# Fuel-Gauge.net
KiCad netlist of a schematic drawn in Altium Designer
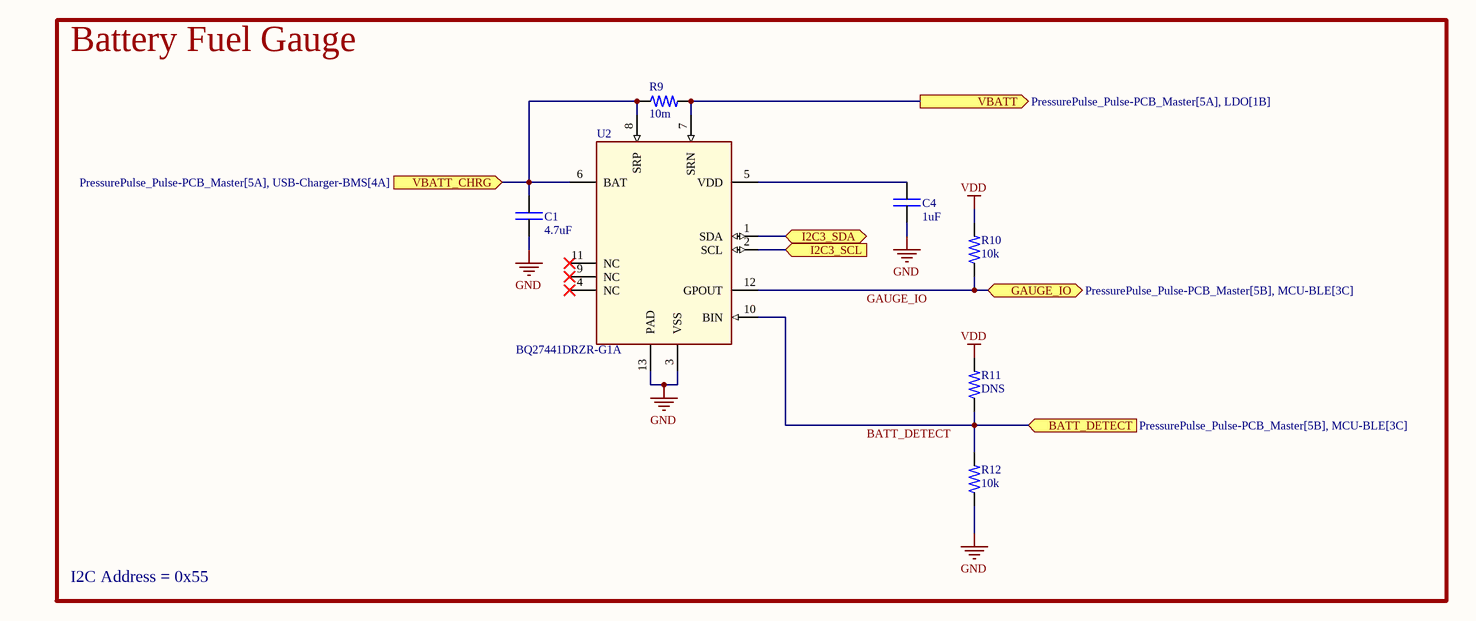
[diagram p0: Fuel-Gauge.SchDoc]

(export (version "E")
  (design (tool "Eeschema 10.0.6"))
  (components
    (comp (ref "C1")
      (value "4.7uF")
      (footprint "PressurePulse:0402C")
      (description "Capacitor")
      (fields (field (name "Comment") "CAP"))
      (libsource (lib "PressurePulse") (part "CAP"))
    )
    (comp (ref "C4")
      (value "1uF")
      (footprint "PressurePulse:0402C")
      (description "Capacitor")
      (fields (field (name "Comment") "CAP"))
      (libsource (lib "PressurePulse") (part "CAP"))
    )
    (comp (ref "R9")
      (value "10m")
      (footprint "PressurePulse:0805R")
      (description "Resistor")
      (fields (field (name "MFR") "YAGEO") (field (name "TOLERANCE") "1%"))
      (libsource (lib "PressurePulse") (part "RES"))
    )
    (comp (ref "R10")
      (value "10k")
      (footprint "PressurePulse:0402R")
      (description "Resistor")
      (fields (field (name "Comment") "RES"))
      (libsource (lib "PressurePulse") (part "RES"))
    )
    (comp (ref "R11")
      (value "DNS")
      (footprint "PressurePulse:0402R")
      (description "Resistor")
      (fields (field (name "Comment") "RES"))
      (libsource (lib "PressurePulse") (part "RES"))
    )
    (comp (ref "R12")
      (value "10k")
      (footprint "PressurePulse:0402R")
      (description "Resistor")
      (fields (field (name "Comment") "RES"))
      (libsource (lib "PressurePulse") (part "RES"))
    )
    (comp (ref "U2")
      (value "BQ27441DRZR-G1A")
      (footprint "PressurePulse:bq27441-G1")
      (description "No Description Available")
      (fields (field (name "MFR") "Texas Instruments"))
      (libsource (lib "PressurePulse") (part "BATT FUEL GAUGE"))
    )
  )
  (nets
    (net (code "1") (name "/BATT_DETECT") (class "Default")
      (node (ref "R11") (pin "1") (pinfunction "1_1") (pintype "passive"))
      (node (ref "R12") (pin "2") (pinfunction "2_2") (pintype "passive"))
      (node (ref "U2") (pin "10") (pinfunction "BIN_10") (pintype "input"))
    )
    (net (code "2") (name "/GAUGE_IO") (class "Default")
      (node (ref "R10") (pin "1") (pinfunction "1_1") (pintype "passive"))
      (node (ref "U2") (pin "12") (pinfunction "GPOUT_12") (pintype "open_collector"))
    )
    (net (code "3") (name "/I2C3_SCL") (class "Default")
      (node (ref "U2") (pin "2") (pinfunction "SCL_2") (pintype "bidirectional"))
    )
    (net (code "4") (name "/I2C3_SDA") (class "Default")
      (node (ref "U2") (pin "1") (pinfunction "SDA_1") (pintype "bidirectional"))
    )
    (net (code "5") (name "/VBATT") (class "Default")
      (node (ref "R9") (pin "2") (pinfunction "2_2") (pintype "passive"))
      (node (ref "U2") (pin "7") (pinfunction "SRN_7") (pintype "input"))
    )
    (net (code "6") (name "/VBATT_CHRG") (class "Default")
      (node (ref "C1") (pin "2") (pinfunction "2_2") (pintype "passive"))
      (node (ref "R9") (pin "1") (pinfunction "1_1") (pintype "passive"))
      (node (ref "U2") (pin "6") (pinfunction "BAT_6") (pintype "power_in"))
      (node (ref "U2") (pin "8") (pinfunction "SRP_8") (pintype "input"))
    )
    (net (code "7") (name "GND") (class "Default")
      (node (ref "C1") (pin "1") (pinfunction "1_1") (pintype "passive"))
      (node (ref "C4") (pin "1") (pinfunction "1_1") (pintype "passive"))
      (node (ref "R12") (pin "1") (pinfunction "1_1") (pintype "passive"))
      (node (ref "U2") (pin "13") (pinfunction "PAD_13") (pintype "power_in"))
      (node (ref "U2") (pin "3") (pinfunction "VSS_3") (pintype "power_in"))
    )
    (net (code "8") (name "Net-(U2-VDD)") (class "Default")
      (node (ref "C4") (pin "2") (pinfunction "2_2") (pintype "passive"))
      (node (ref "U2") (pin "5") (pinfunction "VDD_5") (pintype "power_in"))
    )
    (net (code "9") (name "VDD") (class "Default")
      (node (ref "R10") (pin "2") (pinfunction "2_2") (pintype "passive"))
      (node (ref "R11") (pin "2") (pinfunction "2_2") (pintype "passive"))
    )
    (net (code "10") (name "unconnected-(U2-NC-Pad4)") (class "Default")
      (node (ref "U2") (pin "4") (pinfunction "NC_4") (pintype "passive+no_connect"))
    )
    (net (code "11") (name "unconnected-(U2-NC-Pad9)") (class "Default")
      (node (ref "U2") (pin "9") (pinfunction "NC_9") (pintype "passive+no_connect"))
    )
    (net (code "12") (name "unconnected-(U2-NC-Pad11)") (class "Default")
      (node (ref "U2") (pin "11") (pinfunction "NC_11") (pintype "passive+no_connect"))
    )
  )
)
